# NanoHat-SPDIF.net
KiCad netlist of a schematic drawn in EAGLE
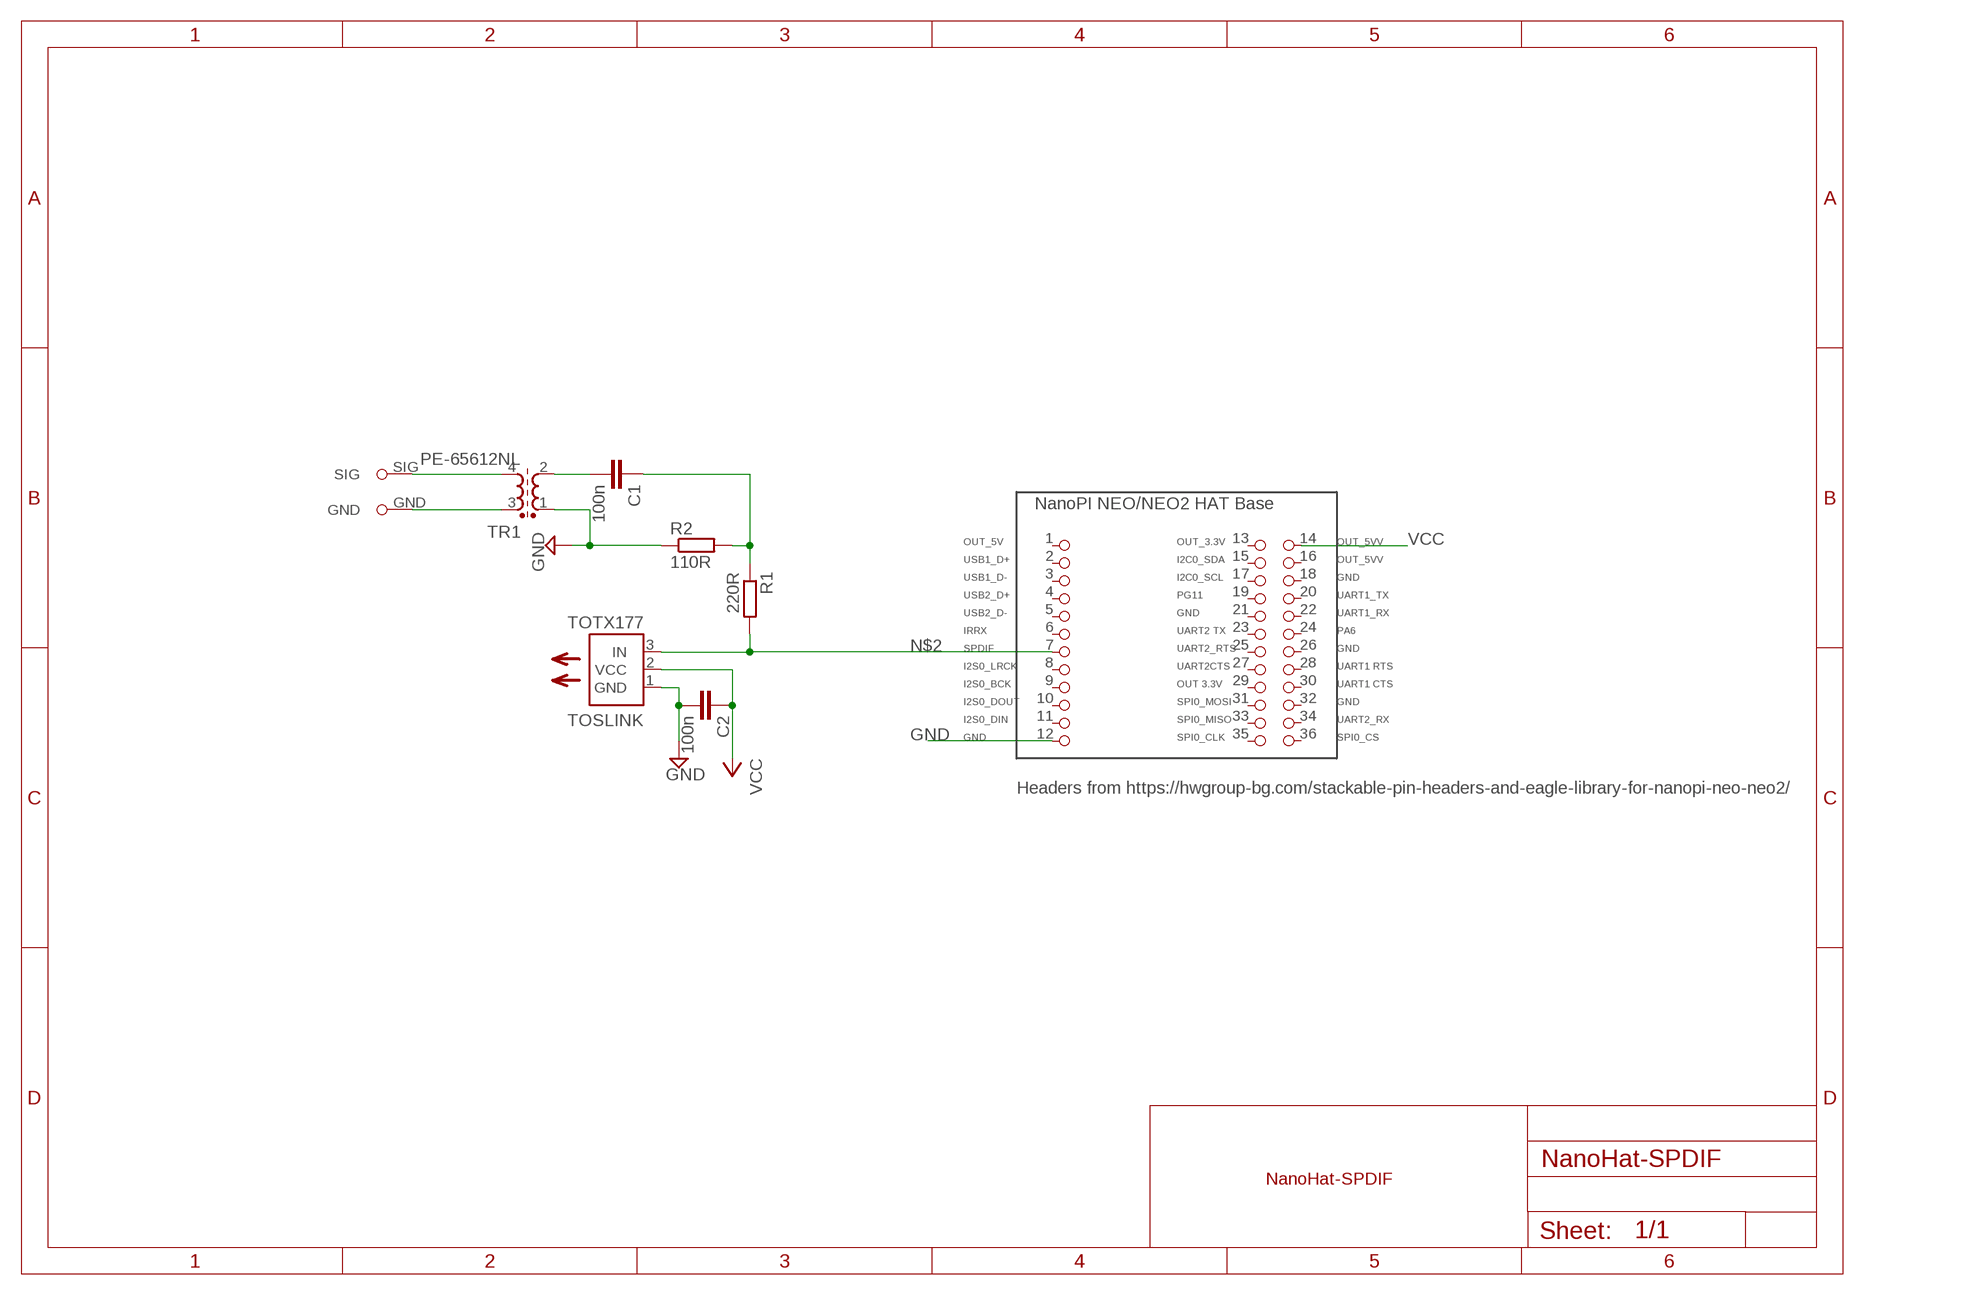
[diagram p0: schematic, sheet 1]

(export (version "E")
  (design (tool "Eeschema 10.0.6"))
  (components
    (comp (ref "C1")
      (value "100n")
      (footprint "eagle-import:C025-024X044")
      (libsource (lib "eagle-import") (part "C-EU025-024X044"))
    )
    (comp (ref "C2")
      (value "100n")
      (footprint "eagle-import:C025-024X044")
      (libsource (lib "eagle-import") (part "C-EU025-024X044"))
    )
    (comp (ref "R1")
      (value "220R")
      (footprint "eagle-import:R0805")
      (libsource (lib "eagle-import") (part "R-EU_R0805"))
    )
    (comp (ref "R2")
      (value "110R")
      (footprint "eagle-import:R0805")
      (libsource (lib "eagle-import") (part "R-EU_R0805"))
    )
    (comp (ref "TOSLINK")
      (value "TOTX177")
      (footprint "eagle-import:TOTX")
      (libsource (lib "eagle-import") (part "TOTX177(F,T)"))
    )
    (comp (ref "TR1")
      (value "PE-65612NL")
      (footprint "eagle-import:S22083")
      (libsource (lib "eagle-import") (part "S22083"))
    )
    (comp (ref "U$1")
      (value "NANO")
      (footprint "eagle-import:NANOPI_NEO_HAT")
      (libsource (lib "eagle-import") (part "NANO"))
    )
    (comp (ref "U$2")
      (value "AV-8.4-5")
      (footprint "eagle-import:AUDIO")
      (libsource (lib "eagle-import") (part "AV-8.4-5"))
    )
  )
  (nets
    (net (code "1") (name "/N$2") (class "Default")
      (node (ref "R1") (pin "2") (pinfunction "2_2") (pintype "passive"))
      (node (ref "TOSLINK") (pin "3") (pinfunction "IN_3") (pintype "input"))
      (node (ref "U$1") (pin "7") (pinfunction "SPDIF_P_7_7") (pintype "passive"))
    )
    (net (code "2") (name "GND") (class "Default")
      (node (ref "C2") (pin "2") (pinfunction "2_2") (pintype "passive"))
      (node (ref "R2") (pin "1") (pinfunction "1_1") (pintype "passive"))
      (node (ref "TOSLINK") (pin "1") (pinfunction "GND_1") (pintype "power_in"))
      (node (ref "TR1") (pin "1") (pinfunction "1_1") (pintype "passive"))
      (node (ref "U$1") (pin "12") (pinfunction "GND_12_12") (pintype "passive"))
    )
    (net (code "3") (name "Net-(C1-Pad1)") (class "Default")
      (node (ref "C1") (pin "1") (pinfunction "1_1") (pintype "passive"))
      (node (ref "R1") (pin "1") (pinfunction "1_1") (pintype "passive"))
      (node (ref "R2") (pin "2") (pinfunction "2_2") (pintype "passive"))
    )
    (net (code "4") (name "Net-(C1-Pad2)") (class "Default")
      (node (ref "C1") (pin "2") (pinfunction "2_2") (pintype "passive"))
      (node (ref "TR1") (pin "2") (pinfunction "2_2") (pintype "passive"))
    )
    (net (code "5") (name "Net-(TR1-Pad3)") (class "Default")
      (node (ref "TR1") (pin "3") (pinfunction "3_3") (pintype "passive"))
      (node (ref "U$2") (pin "GND") (pinfunction "GND_GND") (pintype "bidirectional"))
    )
    (net (code "6") (name "Net-(TR1-Pad4)") (class "Default")
      (node (ref "TR1") (pin "4") (pinfunction "4_4") (pintype "passive"))
      (node (ref "U$2") (pin "SIG") (pinfunction "SIG_SIG") (pintype "bidirectional"))
    )
    (net (code "7") (name "VCC") (class "Default")
      (node (ref "C2") (pin "1") (pinfunction "1_1") (pintype "passive"))
      (node (ref "TOSLINK") (pin "2") (pinfunction "VCC_2") (pintype "power_in"))
      (node (ref "U$1") (pin "14") (pinfunction "OUT_5V_14_14") (pintype "passive"))
    )
    (net (code "8") (name "unconnected-(U$1-3V3_29-Pad29)") (class "Default")
      (node (ref "U$1") (pin "29") (pinfunction "3V3_29_29") (pintype "passive"))
    )
    (net (code "9") (name "unconnected-(U$1-BCK_9-Pad9)") (class "Default")
      (node (ref "U$1") (pin "9") (pinfunction "BCK_9_9") (pintype "passive"))
    )
    (net (code "10") (name "unconnected-(U$1-DIN_11-Pad11)") (class "Default")
      (node (ref "U$1") (pin "11") (pinfunction "DIN_11_11") (pintype "passive"))
    )
    (net (code "11") (name "unconnected-(U$1-DOUT_10-Pad10)") (class "Default")
      (node (ref "U$1") (pin "10") (pinfunction "DOUT_10_10") (pintype "passive"))
    )
    (net (code "12") (name "unconnected-(U$1-GND26-Pad26)") (class "Default")
      (node (ref "U$1") (pin "26") (pinfunction "GND26_26") (pintype "passive"))
    )
    (net (code "13") (name "unconnected-(U$1-GND_18-Pad18)") (class "Default")
      (node (ref "U$1") (pin "18") (pinfunction "GND_18_18") (pintype "passive"))
    )
    (net (code "14") (name "unconnected-(U$1-GND_21-Pad21)") (class "Default")
      (node (ref "U$1") (pin "21") (pinfunction "GND_21_21") (pintype "passive"))
    )
    (net (code "15") (name "unconnected-(U$1-GND_32-Pad32)") (class "Default")
      (node (ref "U$1") (pin "32") (pinfunction "GND_32_32") (pintype "passive"))
    )
    (net (code "16") (name "unconnected-(U$1-I2C0_SCL_17-Pad17)") (class "Default")
      (node (ref "U$1") (pin "17") (pinfunction "I2C0_SCL_17_17") (pintype "passive"))
    )
    (net (code "17") (name "unconnected-(U$1-I2C0_SDA_15-Pad15)") (class "Default")
      (node (ref "U$1") (pin "15") (pinfunction "I2C0_SDA_15_15") (pintype "passive"))
    )
    (net (code "18") (name "unconnected-(U$1-IR_RX_6-Pad6)") (class "Default")
      (node (ref "U$1") (pin "6") (pinfunction "IR_RX_6_6") (pintype "passive"))
    )
    (net (code "19") (name "unconnected-(U$1-LRCK_8-Pad8)") (class "Default")
      (node (ref "U$1") (pin "8") (pinfunction "LRCK_8_8") (pintype "passive"))
    )
    (net (code "20") (name "unconnected-(U$1-MOSI_31-Pad31)") (class "Default")
      (node (ref "U$1") (pin "31") (pinfunction "MOSI_31_31") (pintype "passive"))
    )
    (net (code "21") (name "unconnected-(U$1-OUT_3.3V_13-Pad13)") (class "Default")
      (node (ref "U$1") (pin "13") (pinfunction "OUT_3.3V_13_13") (pintype "passive"))
    )
    (net (code "22") (name "unconnected-(U$1-OUT_5V_16-Pad16)") (class "Default")
      (node (ref "U$1") (pin "16") (pinfunction "OUT_5V_16_16") (pintype "passive"))
    )
    (net (code "23") (name "unconnected-(U$1-OUT_5V_P1-Pad1)") (class "Default")
      (node (ref "U$1") (pin "1") (pinfunction "OUT_5V_P1_1") (pintype "passive"))
    )
    (net (code "24") (name "unconnected-(U$1-PA6_24-Pad24)") (class "Default")
      (node (ref "U$1") (pin "24") (pinfunction "PA6_24_24") (pintype "passive"))
    )
    (net (code "25") (name "unconnected-(U$1-PG11_19-Pad19)") (class "Default")
      (node (ref "U$1") (pin "19") (pinfunction "PG11_19_19") (pintype "passive"))
    )
    (net (code "26") (name "unconnected-(U$1-SPI0_CLK_35-Pad35)") (class "Default")
      (node (ref "U$1") (pin "35") (pinfunction "SPI0_CLK_35_35") (pintype "passive"))
    )
    (net (code "27") (name "unconnected-(U$1-SPI0_MISO_33-Pad33)") (class "Default")
      (node (ref "U$1") (pin "33") (pinfunction "SPI0_MISO_33_33") (pintype "passive"))
    )
    (net (code "28") (name "unconnected-(U$1-SPI_0_CS_36-Pad36)") (class "Default")
      (node (ref "U$1") (pin "36") (pinfunction "SPI_0_CS_36_36") (pintype "passive"))
    )
    (net (code "29") (name "unconnected-(U$1-UART1_CTS_30-Pad30)") (class "Default")
      (node (ref "U$1") (pin "30") (pinfunction "UART1_CTS_30_30") (pintype "passive"))
    )
    (net (code "30") (name "unconnected-(U$1-UART1_RTS_28-Pad28)") (class "Default")
      (node (ref "U$1") (pin "28") (pinfunction "UART1_RTS_28_28") (pintype "passive"))
    )
    (net (code "31") (name "unconnected-(U$1-UART1_RX_22-Pad22)") (class "Default")
      (node (ref "U$1") (pin "22") (pinfunction "UART1_RX_22_22") (pintype "passive"))
    )
    (net (code "32") (name "unconnected-(U$1-UART1_TX_20-Pad20)") (class "Default")
      (node (ref "U$1") (pin "20") (pinfunction "UART1_TX_20_20") (pintype "passive"))
    )
    (net (code "33") (name "unconnected-(U$1-UART2TX_23-Pad23)") (class "Default")
      (node (ref "U$1") (pin "23") (pinfunction "UART2TX_23_23") (pintype "passive"))
    )
    (net (code "34") (name "unconnected-(U$1-UART2_CTS_27-Pad27)") (class "Default")
      (node (ref "U$1") (pin "27") (pinfunction "UART2_CTS_27_27") (pintype "passive"))
    )
    (net (code "35") (name "unconnected-(U$1-UART2_RTS_25-Pad25)") (class "Default")
      (node (ref "U$1") (pin "25") (pinfunction "UART2_RTS_25_25") (pintype "passive"))
    )
    (net (code "36") (name "unconnected-(U$1-UART2_RX_34-Pad34)") (class "Default")
      (node (ref "U$1") (pin "34") (pinfunction "UART2_RX_34_34") (pintype "passive"))
    )
    (net (code "37") (name "unconnected-(U$1-USB_1_D+_2-Pad2)") (class "Default")
      (node (ref "U$1") (pin "2") (pinfunction "USB_1_D+_2_2") (pintype "passive"))
    )
    (net (code "38") (name "unconnected-(U$1-USB_1_D-_3-Pad3)") (class "Default")
      (node (ref "U$1") (pin "3") (pinfunction "USB_1_D-_3_3") (pintype "passive"))
    )
    (net (code "39") (name "unconnected-(U$1-USB_2_D+_4-Pad4)") (class "Default")
      (node (ref "U$1") (pin "4") (pinfunction "USB_2_D+_4_4") (pintype "passive"))
    )
    (net (code "40") (name "unconnected-(U$1-USB_2_D-_5-Pad5)") (class "Default")
      (node (ref "U$1") (pin "5") (pinfunction "USB_2_D-_5_5") (pintype "passive"))
    )
  )
)
